# ASBB_VarBuck.net
KiCad netlist of a schematic drawn in Altium Designer
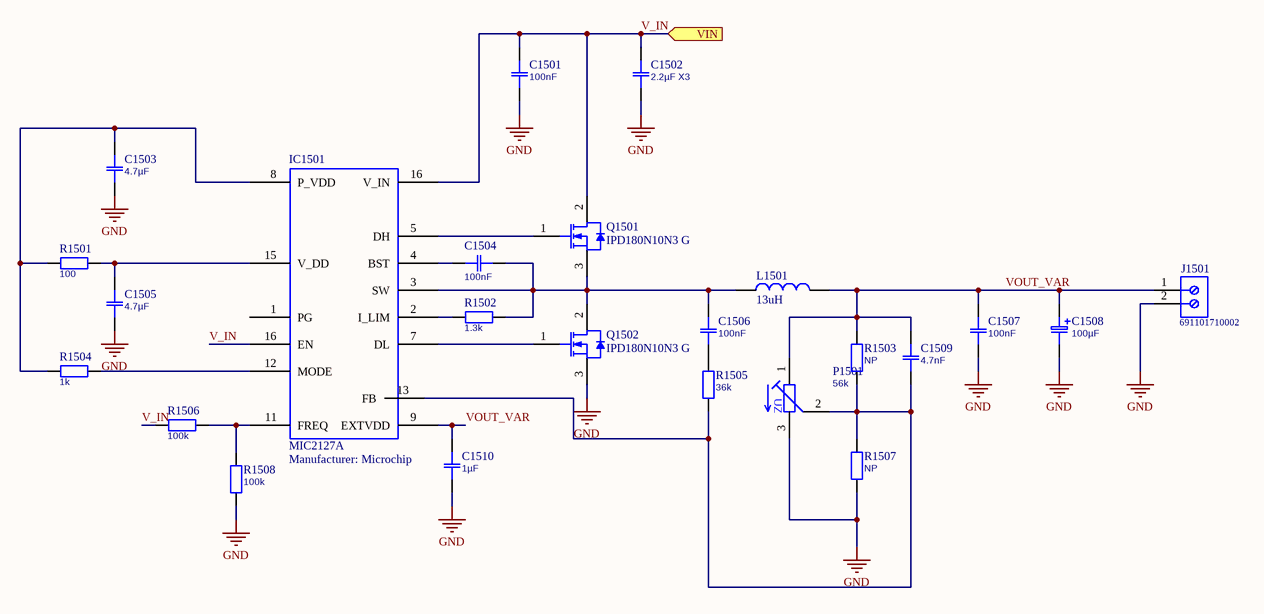
[diagram p0: ASBB_VarBuck.SchDoc]

(export (version "E")
  (design (tool "Eeschema 10.0.6"))
  (components
    (comp (ref "C1501")
      (value "100nF")
      (footprint "CAP 1206/3216")
      (description "Capacitor")
      (fields (field (name "PARTNUMBER") "?"))
      (libsource (lib "FZI") (part "Capacitor"))
    )
    (comp (ref "C1502")
      (value "2.2µF X3")
      (footprint "CAP 1206/3216")
      (description "Capacitor")
      (fields (field (name "PARTNUMBER") "?"))
      (libsource (lib "FZI") (part "Capacitor"))
    )
    (comp (ref "C1503")
      (value "4.7µF")
      (footprint "CAP 1206/3216")
      (description "Capacitor")
      (fields (field (name "PARTNUMBER") "?"))
      (libsource (lib "FZI") (part "Capacitor"))
    )
    (comp (ref "C1504")
      (value "100nF")
      (footprint "Passives:CAP 1206/3216")
      (description "Capacitor")
      (fields (field (name "PARTNUMBER") "?"))
      (libsource (lib "FZI") (part "Capacitor"))
    )
    (comp (ref "C1505")
      (value "4.7µF")
      (footprint "CAP 1206/3216")
      (description "Capacitor")
      (fields (field (name "PARTNUMBER") "?"))
      (libsource (lib "FZI") (part "Capacitor"))
    )
    (comp (ref "C1506")
      (value "100nF")
      (footprint "0603")
      (description "Capacitor")
      (fields (field (name "PARTNUMBER") "?"))
      (libsource (lib "FZI") (part "Capacitor"))
    )
    (comp (ref "C1507")
      (value "100nF")
      (footprint "0603")
      (description "Capacitor")
      (fields (field (name "PARTNUMBER") "?"))
      (libsource (lib "FZI") (part "Capacitor"))
    )
    (comp (ref "C1508")
      (value "100µF")
      (footprint "Passives:CAP ALUM 6.6MM")
      (description "Capacitor, polarised")
      (fields (field (name "PARTNUMBER") "?"))
      (libsource (lib "FZI") (part "Capacitor polarised"))
    )
    (comp (ref "C1509")
      (value "4.7nF")
      (footprint "0603")
      (description "Capacitor")
      (fields (field (name "PARTNUMBER") "?"))
      (libsource (lib "FZI") (part "Capacitor"))
    )
    (comp (ref "C1510")
      (value "1µF")
      (footprint "0603")
      (description "Capacitor")
      (fields (field (name "PARTNUMBER") "?"))
      (libsource (lib "FZI") (part "Capacitor"))
    )
    (comp (ref "IC1501")
      (value "MIC2127A")
      (footprint "MCHP-QFN-MG16_N")
      (description "75V, Synchronous Buck Controller Featuring ADaptive On-Time Control")
      (fields (field (name "MANUFACTURER") "Microchip"))
      (libsource (lib "ASBB") (part "MIC2127A"))
    )
    (comp (ref "J1501")
      (value "691101710002")
      (footprint "691101710002")
      (description "Series 101 - 5.00 mm Horizontal Entry Modular with Pressure Clamp WR-TBL, 2 pin")
      (fields (field (name "PUBLISHER") "Wurth Elektronik"))
      (libsource (lib "Altium_WR-TBL_Wire_Protector_System (rev18a)") (part "691101710002"))
    )
    (comp (ref "L1501")
      (value "13uH")
      (footprint "WE-HCI_1365_WE-PERM")
      (description "WE-HCI SMD Flat Wire High Current Inductor, size 1365, 10A, 13uH")
      (fields (field (name "PART NUMBER") "7443551131") (field (name "PUBLISHER") "Wurth Elektronik"))
      (libsource (lib "ALTIUM-WE-HCI-rev17a") (part "7443551131"))
    )
    (comp (ref "P1501")
      (value "56k")
      (footprint "FZI:Model 43 Trimmer")
      (description "Potentiometer")
      (fields (field (name "PARTNUMBER") "?"))
      (libsource (lib "FZI") (part "Potentiometer"))
    )
    (comp (ref "Q1501")
      (value "IPD180N10N3 G")
      (footprint "INF-PG-TO252-3-11_A_N")
      (fields (field (name "MANUFACTURER") "Infineon"))
      (libsource (lib "Infineon_Power_MOSFET") (part "IPD180N10N3 G"))
    )
    (comp (ref "Q1502")
      (value "IPD180N10N3 G")
      (footprint "INF-PG-TO252-3-11_A_N")
      (fields (field (name "MANUFACTURER") "Infineon"))
      (libsource (lib "Infineon_Power_MOSFET") (part "IPD180N10N3 G"))
    )
    (comp (ref "R1501")
      (value "100")
      (footprint "0603")
      (description "Resistor")
      (fields (field (name "PARTNUMBER") "?"))
      (libsource (lib "FZI") (part "Resistor"))
    )
    (comp (ref "R1502")
      (value "1.3k")
      (footprint "0603")
      (description "Resistor")
      (fields (field (name "PARTNUMBER") "?"))
      (libsource (lib "FZI") (part "Resistor"))
    )
    (comp (ref "R1503")
      (value "NP")
      (footprint "0603")
      (description "Resistor")
      (fields (field (name "PARTNUMBER") "?"))
      (libsource (lib "FZI") (part "Resistor"))
    )
    (comp (ref "R1504")
      (value "1k")
      (footprint "0603")
      (description "Resistor")
      (fields (field (name "PARTNUMBER") "?"))
      (libsource (lib "FZI") (part "Resistor"))
    )
    (comp (ref "R1505")
      (value "36k")
      (footprint "0603")
      (description "Resistor")
      (fields (field (name "PARTNUMBER") "?"))
      (libsource (lib "FZI") (part "Resistor"))
    )
    (comp (ref "R1506")
      (value "100k")
      (footprint "CAP 1206/3216")
      (description "Resistor")
      (fields (field (name "PARTNUMBER") "?"))
      (libsource (lib "FZI") (part "Resistor"))
    )
    (comp (ref "R1507")
      (value "NP")
      (footprint "0603")
      (description "Resistor")
      (fields (field (name "PARTNUMBER") "?"))
      (libsource (lib "FZI") (part "Resistor"))
    )
    (comp (ref "R1508")
      (value "100k")
      (footprint "CAP 1206/3216")
      (description "Resistor")
      (fields (field (name "PARTNUMBER") "?"))
      (libsource (lib "FZI") (part "Resistor"))
    )
  )
  (nets
    (net (code "1") (name "/VOUT_VAR") (class "Default")
      (node (ref "C1507") (pin "1") (pinfunction "1_1") (pintype "passive"))
      (node (ref "C1508") (pin "1") (pinfunction "+_1") (pintype "passive"))
      (node (ref "C1509") (pin "1") (pinfunction "1_1") (pintype "passive"))
      (node (ref "C1510") (pin "1") (pinfunction "1_1") (pintype "passive"))
      (node (ref "IC1501") (pin "9") (pinfunction "EXTVDD_9") (pintype "power_in"))
      (node (ref "J1501") (pin "1") (pinfunction "1_1") (pintype "passive"))
      (node (ref "L1501") (pin "2") (pinfunction "2_2") (pintype "passive"))
      (node (ref "P1501") (pin "1") (pinfunction "1_1") (pintype "passive"))
      (node (ref "R1503") (pin "2") (pinfunction "2_2") (pintype "passive"))
    )
    (net (code "2") (name "/V_IN") (class "Default")
      (node (ref "C1501") (pin "2") (pinfunction "2_2") (pintype "passive"))
      (node (ref "C1502") (pin "2") (pinfunction "2_2") (pintype "passive"))
      (node (ref "IC1501") (pin "16") (pinfunction "EN_16") (pintype "power_in"))
      (node (ref "Q1501") (pin "2") (pinfunction "DRAIN_2") (pintype "passive"))
      (node (ref "R1506") (pin "1") (pinfunction "1_1") (pintype "passive"))
    )
    (net (code "3") (name "GND") (class "Default")
      (node (ref "C1501") (pin "1") (pinfunction "1_1") (pintype "passive"))
      (node (ref "C1502") (pin "1") (pinfunction "1_1") (pintype "passive"))
      (node (ref "C1503") (pin "2") (pinfunction "2_2") (pintype "passive"))
      (node (ref "C1505") (pin "2") (pinfunction "2_2") (pintype "passive"))
      (node (ref "C1507") (pin "2") (pinfunction "2_2") (pintype "passive"))
      (node (ref "C1508") (pin "2") (pinfunction "-_2") (pintype "passive"))
      (node (ref "C1510") (pin "2") (pinfunction "2_2") (pintype "passive"))
      (node (ref "J1501") (pin "2") (pinfunction "2_2") (pintype "passive"))
      (node (ref "P1501") (pin "3") (pinfunction "3_3") (pintype "passive"))
      (node (ref "Q1502") (pin "3") (pinfunction "SOURCE_3") (pintype "passive"))
      (node (ref "R1507") (pin "1") (pinfunction "1_1") (pintype "passive"))
      (node (ref "R1508") (pin "1") (pinfunction "1_1") (pintype "passive"))
    )
    (net (code "4") (name "Net-(C1506-Pad2)") (class "Default")
      (node (ref "C1506") (pin "2") (pinfunction "2_2") (pintype "passive"))
      (node (ref "R1505") (pin "2") (pinfunction "2_2") (pintype "passive"))
    )
    (net (code "5") (name "Net-(IC1501-BST)") (class "Default")
      (node (ref "C1504") (pin "2") (pinfunction "2_2") (pintype "passive"))
      (node (ref "IC1501") (pin "4") (pinfunction "BST_4") (pintype "power_in"))
    )
    (net (code "6") (name "Net-(IC1501-DH)") (class "Default")
      (node (ref "IC1501") (pin "5") (pinfunction "DH_5") (pintype "power_in"))
      (node (ref "Q1501") (pin "1") (pinfunction "GATE_1") (pintype "passive"))
    )
    (net (code "7") (name "Net-(IC1501-DL)") (class "Default")
      (node (ref "IC1501") (pin "7") (pinfunction "DL_7") (pintype "power_in"))
      (node (ref "Q1502") (pin "1") (pinfunction "GATE_1") (pintype "passive"))
    )
    (net (code "8") (name "Net-(IC1501-FB)") (class "Default")
      (node (ref "C1509") (pin "2") (pinfunction "2_2") (pintype "passive"))
      (node (ref "IC1501") (pin "13") (pinfunction "FB_13") (pintype "power_in"))
      (node (ref "P1501") (pin "2") (pinfunction "2_2") (pintype "passive"))
      (node (ref "R1503") (pin "1") (pinfunction "1_1") (pintype "passive"))
      (node (ref "R1505") (pin "1") (pinfunction "1_1") (pintype "passive"))
      (node (ref "R1507") (pin "2") (pinfunction "2_2") (pintype "passive"))
    )
    (net (code "9") (name "Net-(IC1501-FREQ)") (class "Default")
      (node (ref "IC1501") (pin "11") (pinfunction "FREQ_11") (pintype "power_in"))
      (node (ref "R1506") (pin "2") (pinfunction "2_2") (pintype "passive"))
      (node (ref "R1508") (pin "2") (pinfunction "2_2") (pintype "passive"))
    )
    (net (code "10") (name "Net-(IC1501-I_LIM)") (class "Default")
      (node (ref "IC1501") (pin "2") (pinfunction "I_LIM_2") (pintype "power_in"))
      (node (ref "R1502") (pin "1") (pinfunction "1_1") (pintype "passive"))
    )
    (net (code "11") (name "Net-(IC1501-MODE)") (class "Default")
      (node (ref "IC1501") (pin "12") (pinfunction "MODE_12") (pintype "power_in"))
      (node (ref "R1504") (pin "2") (pinfunction "2_2") (pintype "passive"))
    )
    (net (code "12") (name "Net-(IC1501-P_VDD)") (class "Default")
      (node (ref "C1503") (pin "1") (pinfunction "1_1") (pintype "passive"))
      (node (ref "IC1501") (pin "8") (pinfunction "P_VDD_8") (pintype "passive"))
      (node (ref "R1501") (pin "1") (pinfunction "1_1") (pintype "passive"))
      (node (ref "R1504") (pin "1") (pinfunction "1_1") (pintype "passive"))
    )
    (net (code "13") (name "Net-(IC1501-SW)") (class "Default")
      (node (ref "C1504") (pin "1") (pinfunction "1_1") (pintype "passive"))
      (node (ref "C1506") (pin "1") (pinfunction "1_1") (pintype "passive"))
      (node (ref "IC1501") (pin "3") (pinfunction "SW_3") (pintype "power_in"))
      (node (ref "L1501") (pin "1") (pinfunction "1_1") (pintype "passive"))
      (node (ref "Q1501") (pin "3") (pinfunction "SOURCE_3") (pintype "passive"))
      (node (ref "Q1502") (pin "2") (pinfunction "DRAIN_2") (pintype "passive"))
      (node (ref "R1502") (pin "2") (pinfunction "2_2") (pintype "passive"))
    )
    (net (code "14") (name "Net-(IC1501-V_DD)") (class "Default")
      (node (ref "C1505") (pin "1") (pinfunction "1_1") (pintype "passive"))
      (node (ref "IC1501") (pin "15") (pinfunction "V_DD_15") (pintype "power_in"))
      (node (ref "R1501") (pin "2") (pinfunction "2_2") (pintype "passive"))
    )
    (net (code "15") (name "unconnected-(IC1501-PG-Pad1)") (class "Default")
      (node (ref "IC1501") (pin "1") (pinfunction "PG_1") (pintype "passive"))
    )
  )
)
